# captivate_phone.net
KiCad netlist of a schematic drawn in Altium Designer
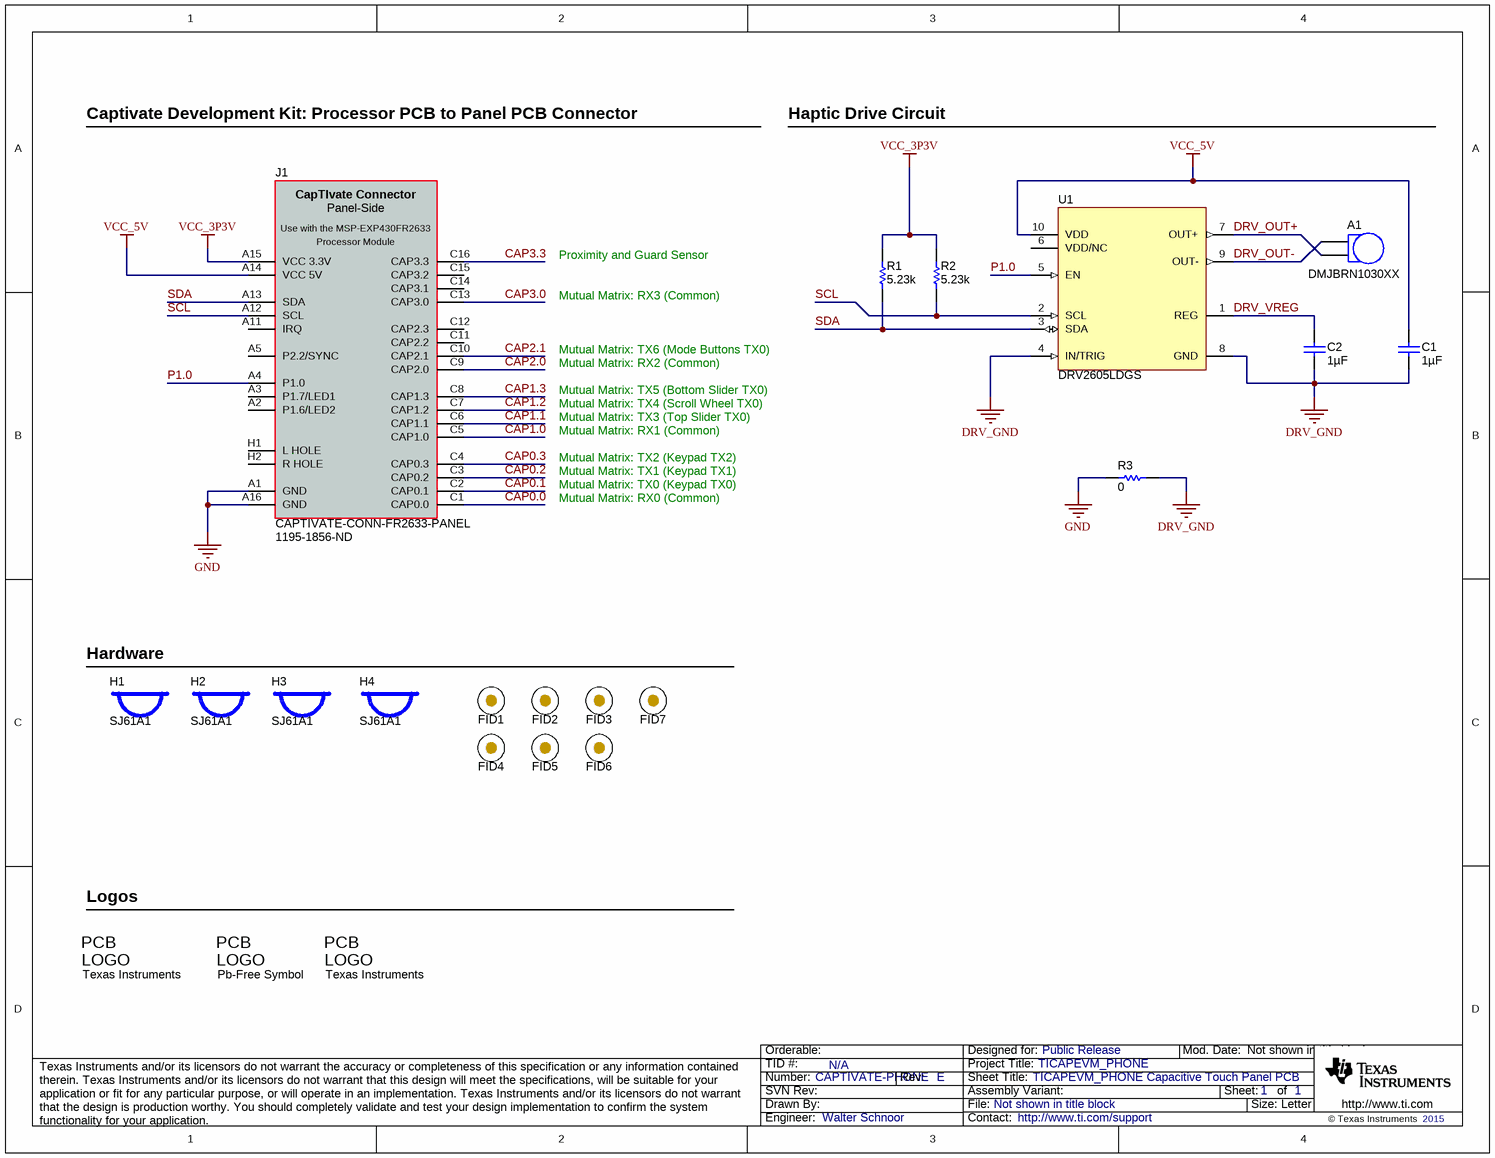
[diagram p0: captivate_phone.SchDoc]

(export (version "E")
  (design (tool "Eeschema 10.0.6"))
  (components
    (comp (ref "A1")
      (value "DMJBRN1030XX")
      (footprint "SEMCO1030")
      (description "Linear Resonant Actuator")
      (fields
        (field (name "MANUFACTURER") "Samsung Electro-Mechanics")
        (field (name "SYMBOLCREATOR") "a0273983")
      )
      (libsource (lib "haptic_actuator") (part "DMJBRN1030XX"))
    )
    (comp (ref "C1")
      (value "C0603C105K8PACTU")
      (footprint "0603")
      (description "CAP, CERM, 1 µF, 10 V, +/- 10%, X5R, 0603")
      (fields
        (field (name "VALUEDISPLAYED") "1µF")
        (field (name "MANUFACTURER") "Kemet")
        (field (name "PUBLISHER") "Texas Instruments")
      )
      (libsource (lib "Capacitor_Ceramic") (part "C0603C105K8PACTU"))
    )
    (comp (ref "C2")
      (value "C0603C105K8PACTU")
      (footprint "0603")
      (description "CAP, CERM, 1 µF, 10 V, +/- 10%, X5R, 0603")
      (fields
        (field (name "VALUEDISPLAYED") "1µF")
        (field (name "MANUFACTURER") "Kemet")
        (field (name "PUBLISHER") "Texas Instruments")
      )
      (libsource (lib "Capacitor_Ceramic") (part "C0603C105K8PACTU"))
    )
    (comp (ref "FID1")
      (value "Fiducial")
      (footprint "Fiducial10-20")
      (description "Fiducial mark.  There is nothing to buy or mount.")
      (fields (field (name "SYMBOLCREATOR") "codlsc") (field (name "PUBLISHER") "Texas Instruments"))
      (libsource (lib "MiscParts") (part "Fiducial"))
    )
    (comp (ref "FID2")
      (value "Fiducial")
      (footprint "Fiducial10-20")
      (description "Fiducial mark.  There is nothing to buy or mount.")
      (fields (field (name "SYMBOLCREATOR") "codlsc") (field (name "PUBLISHER") "Texas Instruments"))
      (libsource (lib "MiscParts") (part "Fiducial"))
    )
    (comp (ref "FID3")
      (value "Fiducial")
      (footprint "Fiducial10-20")
      (description "Fiducial mark.  There is nothing to buy or mount.")
      (fields (field (name "SYMBOLCREATOR") "codlsc") (field (name "PUBLISHER") "Texas Instruments"))
      (libsource (lib "MiscParts") (part "Fiducial"))
    )
    (comp (ref "FID4")
      (value "Fiducial")
      (footprint "Fiducial10-20")
      (description "Fiducial mark.  There is nothing to buy or mount.")
      (fields (field (name "SYMBOLCREATOR") "codlsc") (field (name "PUBLISHER") "Texas Instruments"))
      (libsource (lib "MiscParts") (part "Fiducial"))
    )
    (comp (ref "FID5")
      (value "Fiducial")
      (footprint "Fiducial10-20")
      (description "Fiducial mark.  There is nothing to buy or mount.")
      (fields (field (name "SYMBOLCREATOR") "codlsc") (field (name "PUBLISHER") "Texas Instruments"))
      (libsource (lib "MiscParts") (part "Fiducial"))
    )
    (comp (ref "FID6")
      (value "Fiducial")
      (footprint "Fiducial10-20")
      (description "Fiducial mark.  There is nothing to buy or mount.")
      (fields (field (name "SYMBOLCREATOR") "codlsc") (field (name "PUBLISHER") "Texas Instruments"))
      (libsource (lib "MiscParts") (part "Fiducial"))
    )
    (comp (ref "FID7")
      (value "Fiducial")
      (footprint "Fiducial10-20")
      (description "Fiducial mark.  There is nothing to buy or mount.")
      (fields (field (name "SYMBOLCREATOR") "codlsc") (field (name "PUBLISHER") "Texas Instruments"))
      (libsource (lib "MiscParts") (part "Fiducial"))
    )
    (comp (ref "H1")
      (value "SJ61A1")
      (footprint "Bumpon_SJ61A1")
      (description "Bumpon, Cylindrical, 0.312 X 0.200, Black")
      (fields
        (field (name "MANUFACTURER") "3M")
        (field (name "SYMBOLCREATOR") "a0412235")
        (field (name "PUBLISHER") "Texas Instruments")
      )
      (libsource (lib "Hardware") (part "SJ61A1"))
    )
    (comp (ref "H2")
      (value "SJ61A1")
      (footprint "Bumpon_SJ61A1")
      (description "Bumpon, Cylindrical, 0.312 X 0.200, Black")
      (fields
        (field (name "MANUFACTURER") "3M")
        (field (name "SYMBOLCREATOR") "a0412235")
        (field (name "PUBLISHER") "Texas Instruments")
      )
      (libsource (lib "Hardware") (part "SJ61A1"))
    )
    (comp (ref "H3")
      (value "SJ61A1")
      (footprint "Bumpon_SJ61A1")
      (description "Bumpon, Cylindrical, 0.312 X 0.200, Black")
      (fields
        (field (name "MANUFACTURER") "3M")
        (field (name "SYMBOLCREATOR") "a0412235")
        (field (name "PUBLISHER") "Texas Instruments")
      )
      (libsource (lib "Hardware") (part "SJ61A1"))
    )
    (comp (ref "H4")
      (value "SJ61A1")
      (footprint "Bumpon_SJ61A1")
      (description "Bumpon, Cylindrical, 0.312 X 0.200, Black")
      (fields
        (field (name "MANUFACTURER") "3M")
        (field (name "SYMBOLCREATOR") "a0412235")
        (field (name "PUBLISHER") "Texas Instruments")
      )
      (libsource (lib "Hardware") (part "SJ61A1"))
    )
    (comp (ref "J1")
      (value "CAPTIVATE-CONN-FR2633-PANEL")
      (footprint "CAPTIVATE-CONN-48")
      (description "CapTIvate Panel-Side Connector, 3x16, 100mil, TH, RA, M, MSP-EXP430FR2633")
      (fields
        (field (name "MANUFACTURER") "Used in BOM report")
        (field (name "SUPPLIER PART NUMBER 1") "1195-1856-ND")
        (field (name "SYMBOLCREATOR") "a0273983")
      )
      (libsource (lib "CapTIvate_Connector") (part "CAPTIVATE-CONN-MSP-EXP430FR2633-PANEL"))
    )
    (comp (ref "Logo1")
      (value "Pb-Free Symbol")
      (footprint "Pb-Free_Overlay_Medium")
      (fields (field (name "SYMBOLCREATOR") "a0412235") (field (name "PUBLISHER") "Texas Instruments"))
      (libsource (lib "Logos") (part "Pb-Free"))
    )
    (comp (ref "Logo2")
      (value "Texas Instruments")
      (footprint "TI_Horizontal_Overlay_Medium")
      (description "Texas Instrument Corporate Signature")
      (fields (field (name "SYMBOLCREATOR") "codlsc") (field (name "PUBLISHER") "Texas Instruments"))
      (libsource (lib "Logos") (part "TI_Logo"))
    )
    (comp (ref "Logo3")
      (value "Texas Instruments")
      (footprint "TI_Horizontal_Overlay_Medium")
      (description "Texas Instrument Corporate Signature")
      (fields (field (name "SYMBOLCREATOR") "a0412235") (field (name "PUBLISHER") "Texas Instruments"))
      (libsource (lib "Logos") (part "TI_Logo"))
    )
    (comp (ref "R1")
      (value "CRCW06035K23FKEA")
      (footprint "0603")
      (description "RES, 5.23 k, 1%, 0.1 W, 0603")
      (fields
        (field (name "VALUEDISPLAYED") "5.23k")
        (field (name "MANUFACTURER") "Vishay-Dale")
        (field (name "PUBLISHER") "Texas Instruments")
      )
      (libsource (lib "Resistor_0603") (part "CRCW06035K23FKEA"))
    )
    (comp (ref "R2")
      (value "CRCW06035K23FKEA")
      (footprint "0603")
      (description "RES, 5.23 k, 1%, 0.1 W, 0603")
      (fields
        (field (name "VALUEDISPLAYED") "5.23k")
        (field (name "MANUFACTURER") "Vishay-Dale")
        (field (name "PUBLISHER") "Texas Instruments")
      )
      (libsource (lib "Resistor_0603") (part "CRCW06035K23FKEA"))
    )
    (comp (ref "R3")
      (value "CRCW06030000Z0EA")
      (footprint "0603")
      (description "RES, 0, 5%, 0.1 W, 0603")
      (fields
        (field (name "VALUEDISPLAYED") "0")
        (field (name "MANUFACTURER") "Vishay-Dale")
        (field (name "PUBLISHER") "Texas Instruments")
      )
      (libsource (lib "Resistor_0603") (part "CRCW06030000Z0EA"))
    )
    (comp (ref "U1")
      (value "DRV2605LDGS")
      (footprint "DGS0010A_L")
      (description "Haptic Driver for LRA and ERM With Built-In Library and Smart Loop Architecture, DGS0010A")
      (fields
        (field (name "MANUFACTURER") "Texas Instruments")
        (field (name "SYMBOLCREATOR") "a0411947")
        (field (name "PUBLISHER") "Texas Instruments")
      )
      (libsource (lib "TI_Pre_RTM") (part "DRV2605LDGS"))
    )
  )
  (nets
    (net (code "1") (name "/CAP0.0") (class "Default")
      (node (ref "J1") (pin "C1") (pinfunction "CAP0.0_C1") (pintype "passive"))
    )
    (net (code "2") (name "/CAP0.1") (class "Default")
      (node (ref "J1") (pin "C2") (pinfunction "CAP0.1_C2") (pintype "passive"))
    )
    (net (code "3") (name "/CAP0.2") (class "Default")
      (node (ref "J1") (pin "C3") (pinfunction "CAP0.2_C3") (pintype "passive"))
    )
    (net (code "4") (name "/CAP0.3") (class "Default")
      (node (ref "J1") (pin "C4") (pinfunction "CAP0.3_C4") (pintype "passive"))
    )
    (net (code "5") (name "/CAP1.0") (class "Default")
      (node (ref "J1") (pin "C5") (pinfunction "CAP1.0_C5") (pintype "passive"))
    )
    (net (code "6") (name "/CAP1.1") (class "Default")
      (node (ref "J1") (pin "C6") (pinfunction "CAP1.1_C6") (pintype "passive"))
    )
    (net (code "7") (name "/CAP1.2") (class "Default")
      (node (ref "J1") (pin "C7") (pinfunction "CAP1.2_C7") (pintype "passive"))
    )
    (net (code "8") (name "/CAP1.3") (class "Default")
      (node (ref "J1") (pin "C8") (pinfunction "CAP1.3_C8") (pintype "passive"))
    )
    (net (code "9") (name "/CAP2.0") (class "Default")
      (node (ref "J1") (pin "C9") (pinfunction "CAP2.0_C9") (pintype "passive"))
    )
    (net (code "10") (name "/CAP2.1") (class "Default")
      (node (ref "J1") (pin "C10") (pinfunction "CAP2.1_C10") (pintype "passive"))
    )
    (net (code "11") (name "/CAP3.0") (class "Default")
      (node (ref "J1") (pin "C13") (pinfunction "CAP3.0_C13") (pintype "passive"))
    )
    (net (code "12") (name "/CAP3.3") (class "Default")
      (node (ref "J1") (pin "C16") (pinfunction "CAP3.3_C16") (pintype "passive"))
    )
    (net (code "13") (name "/DRV_OUT+") (class "Default")
      (node (ref "A1") (pin "2") (pinfunction "2_2") (pintype "passive"))
      (node (ref "U1") (pin "7") (pinfunction "OUT+_7") (pintype "output"))
    )
    (net (code "14") (name "/DRV_OUT-") (class "Default")
      (node (ref "A1") (pin "1") (pinfunction "1_1") (pintype "passive"))
      (node (ref "U1") (pin "9") (pinfunction "OUT-_9") (pintype "output"))
    )
    (net (code "15") (name "/DRV_VREG") (class "Default")
      (node (ref "C2") (pin "1") (pinfunction "1_1") (pintype "passive"))
      (node (ref "U1") (pin "1") (pinfunction "REG_1") (pintype "power_in"))
    )
    (net (code "16") (name "/P1.0") (class "Default")
      (node (ref "J1") (pin "A4") (pinfunction "P1.0_A4") (pintype "open_collector"))
      (node (ref "U1") (pin "5") (pinfunction "EN_5") (pintype "input"))
    )
    (net (code "17") (name "/SCL") (class "Default")
      (node (ref "J1") (pin "A12") (pinfunction "SCL_A12") (pintype "open_collector"))
      (node (ref "R2") (pin "1") (pinfunction "1_1") (pintype "passive"))
      (node (ref "U1") (pin "2") (pinfunction "SCL_2") (pintype "input"))
    )
    (net (code "18") (name "/SDA") (class "Default")
      (node (ref "J1") (pin "A13") (pinfunction "SDA_A13") (pintype "open_collector"))
      (node (ref "R1") (pin "1") (pinfunction "1_1") (pintype "passive"))
      (node (ref "U1") (pin "3") (pinfunction "SDA_3") (pintype "bidirectional"))
    )
    (net (code "19") (name "DRV_GND") (class "Default")
      (node (ref "C1") (pin "2") (pinfunction "2_2") (pintype "passive"))
      (node (ref "C2") (pin "2") (pinfunction "2_2") (pintype "passive"))
      (node (ref "R3") (pin "1") (pinfunction "1_1") (pintype "passive"))
      (node (ref "U1") (pin "4") (pinfunction "IN/TRIG_4") (pintype "input"))
      (node (ref "U1") (pin "8") (pinfunction "GND_8") (pintype "power_in"))
    )
    (net (code "20") (name "GND") (class "Default")
      (node (ref "J1") (pin "A1") (pinfunction "GND_A1") (pintype "power_in"))
      (node (ref "J1") (pin "A16") (pinfunction "GND_A16") (pintype "power_in"))
      (node (ref "R3") (pin "2") (pinfunction "2_2") (pintype "passive"))
    )
    (net (code "21") (name "VCC_3P3V") (class "Default")
      (node (ref "J1") (pin "A15") (pinfunction "VCC_3.3V_A15") (pintype "power_in"))
      (node (ref "R1") (pin "2") (pinfunction "2_2") (pintype "passive"))
      (node (ref "R2") (pin "2") (pinfunction "2_2") (pintype "passive"))
    )
    (net (code "22") (name "VCC_5V") (class "Default")
      (node (ref "C1") (pin "1") (pinfunction "1_1") (pintype "passive"))
      (node (ref "J1") (pin "A14") (pinfunction "VCC_5V_A14") (pintype "power_in"))
      (node (ref "U1") (pin "10") (pinfunction "VDD_10") (pintype "power_in"))
    )
    (net (code "23") (name "unconnected-(J1-CAP2.2-PadC11)") (class "Default")
      (node (ref "J1") (pin "C11") (pinfunction "CAP2.2_C11") (pintype "passive"))
    )
    (net (code "24") (name "unconnected-(J1-CAP2.3-PadC12)") (class "Default")
      (node (ref "J1") (pin "C12") (pinfunction "CAP2.3_C12") (pintype "passive"))
    )
    (net (code "25") (name "unconnected-(J1-CAP3.1-PadC14)") (class "Default")
      (node (ref "J1") (pin "C14") (pinfunction "CAP3.1_C14") (pintype "passive"))
    )
    (net (code "26") (name "unconnected-(J1-CAP3.2-PadC15)") (class "Default")
      (node (ref "J1") (pin "C15") (pinfunction "CAP3.2_C15") (pintype "passive"))
    )
    (net (code "27") (name "unconnected-(J1-IRQ-PadA11)") (class "Default")
      (node (ref "J1") (pin "A11") (pinfunction "IRQ_A11") (pintype "open_collector"))
    )
    (net (code "28") (name "unconnected-(J1-L_HOLE-PadH1)") (class "Default")
      (node (ref "J1") (pin "H1") (pinfunction "L_HOLE_H1") (pintype "passive"))
    )
    (net (code "29") (name "unconnected-(J1-P1.6{slash}LED2-PadA2)") (class "Default")
      (node (ref "J1") (pin "A2") (pinfunction "P1.6/LED2_A2") (pintype "open_collector"))
    )
    (net (code "30") (name "unconnected-(J1-P1.7{slash}LED1-PadA3)") (class "Default")
      (node (ref "J1") (pin "A3") (pinfunction "P1.7/LED1_A3") (pintype "open_collector"))
    )
    (net (code "31") (name "unconnected-(J1-P2.2{slash}SYNC-PadA5)") (class "Default")
      (node (ref "J1") (pin "A5") (pinfunction "P2.2/SYNC_A5") (pintype "open_collector"))
    )
    (net (code "32") (name "unconnected-(J1-R_HOLE-PadH2)") (class "Default")
      (node (ref "J1") (pin "H2") (pinfunction "R_HOLE_H2") (pintype "passive"))
    )
    (net (code "33") (name "unconnected-(U1-VDD{slash}NC-Pad6)") (class "Default")
      (node (ref "U1") (pin "6") (pinfunction "VDD/NC_6") (pintype "power_in"))
    )
  )
)
